# proto.net
KiCad netlist of a schematic drawn in EAGLE
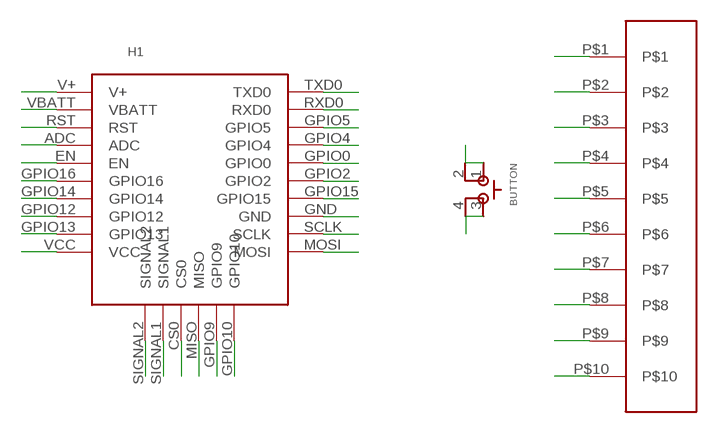
[diagram p0: schematic, sheet 1]

(export (version "E")
  (design (tool "Eeschema 10.0.6"))
  (components
    (comp (ref "BUTTON")
      (value "SKSCLDE010")
      (footprint "eagle-import:SKSCLDE010")
      (libsource (lib "eagle-import") (part "SKSCLDE010"))
    )
    (comp (ref "H1")
      (value "ESP-BOARD")
      (footprint "eagle-import:ESP-BOARD")
      (libsource (lib "eagle-import") (part "ESP-BOARD"))
    )
    (comp (ref "U$1")
      (value "1X10-EDGE")
      (footprint "eagle-import:1X10-EDGE")
      (libsource (lib "eagle-import") (part "1X10-EDGE"))
    )
  )
  (nets
    (net (code "1") (name "Net-(BUTTON-3)") (class "Default")
      (node (ref "BUTTON") (pin "3") (pinfunction "4_3") (pintype "bidirectional"))
      (node (ref "BUTTON") (pin "4") (pinfunction "3_4") (pintype "bidirectional"))
    )
    (net (code "2") (name "Net-(BUTTON-Pad1)") (class "Default")
      (node (ref "BUTTON") (pin "1") (pinfunction "1_1") (pintype "bidirectional"))
      (node (ref "BUTTON") (pin "2") (pinfunction "2_2") (pintype "bidirectional"))
    )
    (net (code "3") (name "unconnected-(H1-PadADC)") (class "Default")
      (node (ref "H1") (pin "ADC") (pinfunction "ADC_ADC") (pintype "bidirectional"))
    )
    (net (code "4") (name "unconnected-(H1-PadCS0)") (class "Default")
      (node (ref "H1") (pin "CS0") (pinfunction "CS0_CS0") (pintype "bidirectional"))
    )
    (net (code "5") (name "unconnected-(H1-PadEN)") (class "Default")
      (node (ref "H1") (pin "EN") (pinfunction "EN_EN") (pintype "bidirectional"))
    )
    (net (code "6") (name "unconnected-(H1-PadGND)") (class "Default")
      (node (ref "H1") (pin "GND") (pinfunction "GND_GND") (pintype "power_in"))
    )
    (net (code "7") (name "unconnected-(H1-PadGPIO0)") (class "Default")
      (node (ref "H1") (pin "GPIO0") (pinfunction "GPIO0_GPIO0") (pintype "bidirectional"))
    )
    (net (code "8") (name "unconnected-(H1-PadGPIO2)") (class "Default")
      (node (ref "H1") (pin "GPIO2") (pinfunction "GPIO2_GPIO2") (pintype "bidirectional"))
    )
    (net (code "9") (name "unconnected-(H1-PadGPIO4)") (class "Default")
      (node (ref "H1") (pin "GPIO4") (pinfunction "GPIO4_GPIO4") (pintype "bidirectional"))
    )
    (net (code "10") (name "unconnected-(H1-PadGPIO5)") (class "Default")
      (node (ref "H1") (pin "GPIO5") (pinfunction "GPIO5_GPIO5") (pintype "bidirectional"))
    )
    (net (code "11") (name "unconnected-(H1-PadGPIO9)") (class "Default")
      (node (ref "H1") (pin "GPIO9") (pinfunction "GPIO9_GPIO9") (pintype "bidirectional"))
    )
    (net (code "12") (name "unconnected-(H1-PadGPIO10)") (class "Default")
      (node (ref "H1") (pin "GPIO10") (pinfunction "GPIO10_GPIO10") (pintype "bidirectional"))
    )
    (net (code "13") (name "unconnected-(H1-PadGPIO12)") (class "Default")
      (node (ref "H1") (pin "GPIO12") (pinfunction "GPIO12_GPIO12") (pintype "bidirectional"))
    )
    (net (code "14") (name "unconnected-(H1-PadGPIO13)") (class "Default")
      (node (ref "H1") (pin "GPIO13") (pinfunction "GPIO13_GPIO13") (pintype "bidirectional"))
    )
    (net (code "15") (name "unconnected-(H1-PadGPIO14)") (class "Default")
      (node (ref "H1") (pin "GPIO14") (pinfunction "GPIO14_GPIO14") (pintype "bidirectional"))
    )
    (net (code "16") (name "unconnected-(H1-PadGPIO15)") (class "Default")
      (node (ref "H1") (pin "GPIO15") (pinfunction "GPIO15_GPIO15") (pintype "bidirectional"))
    )
    (net (code "17") (name "unconnected-(H1-PadGPIO16)") (class "Default")
      (node (ref "H1") (pin "GPIO16") (pinfunction "GPIO16_GPIO16") (pintype "bidirectional"))
    )
    (net (code "18") (name "unconnected-(H1-PadMISO)") (class "Default")
      (node (ref "H1") (pin "MISO") (pinfunction "MISO_MISO") (pintype "bidirectional"))
    )
    (net (code "19") (name "unconnected-(H1-PadMOSI)") (class "Default")
      (node (ref "H1") (pin "MOSI") (pinfunction "MOSI_MOSI") (pintype "bidirectional"))
    )
    (net (code "20") (name "unconnected-(H1-PadRST)") (class "Default")
      (node (ref "H1") (pin "RST") (pinfunction "RST_RST") (pintype "bidirectional"))
    )
    (net (code "21") (name "unconnected-(H1-PadRXD0)") (class "Default")
      (node (ref "H1") (pin "RXD0") (pinfunction "RXD0_RXD0") (pintype "bidirectional"))
    )
    (net (code "22") (name "unconnected-(H1-PadSCLK)") (class "Default")
      (node (ref "H1") (pin "SCLK") (pinfunction "SCLK_SCLK") (pintype "bidirectional"))
    )
    (net (code "23") (name "unconnected-(H1-PadSIGNAL1)") (class "Default")
      (node (ref "H1") (pin "SIGNAL1") (pinfunction "SIGNAL1_SIGNAL1") (pintype "bidirectional"))
    )
    (net (code "24") (name "unconnected-(H1-PadSIGNAL2)") (class "Default")
      (node (ref "H1") (pin "SIGNAL2") (pinfunction "SIGNAL2_SIGNAL2") (pintype "bidirectional"))
    )
    (net (code "25") (name "unconnected-(H1-PadTXD0)") (class "Default")
      (node (ref "H1") (pin "TXD0") (pinfunction "TXD0_TXD0") (pintype "bidirectional"))
    )
    (net (code "26") (name "unconnected-(H1-PadV+)") (class "Default")
      (node (ref "H1") (pin "V+") (pinfunction "V+_V+") (pintype "power_in"))
    )
    (net (code "27") (name "unconnected-(H1-PadVBATT)") (class "Default")
      (node (ref "H1") (pin "VBATT") (pinfunction "VBATT_VBATT") (pintype "power_in"))
    )
    (net (code "28") (name "unconnected-(H1-PadVCC)") (class "Default")
      (node (ref "H1") (pin "VCC") (pinfunction "VCC_VCC") (pintype "power_in"))
    )
    (net (code "29") (name "unconnected-(U$1-PadP$1)") (class "Default")
      (node (ref "U$1") (pin "P$1") (pinfunction "P$1_P$1") (pintype "bidirectional"))
    )
    (net (code "30") (name "unconnected-(U$1-PadP$2)") (class "Default")
      (node (ref "U$1") (pin "P$2") (pinfunction "P$2_P$2") (pintype "bidirectional"))
    )
    (net (code "31") (name "unconnected-(U$1-PadP$3)") (class "Default")
      (node (ref "U$1") (pin "P$3") (pinfunction "P$3_P$3") (pintype "bidirectional"))
    )
    (net (code "32") (name "unconnected-(U$1-PadP$4)") (class "Default")
      (node (ref "U$1") (pin "P$4") (pinfunction "P$4_P$4") (pintype "bidirectional"))
    )
    (net (code "33") (name "unconnected-(U$1-PadP$5)") (class "Default")
      (node (ref "U$1") (pin "P$5") (pinfunction "P$5_P$5") (pintype "bidirectional"))
    )
    (net (code "34") (name "unconnected-(U$1-PadP$6)") (class "Default")
      (node (ref "U$1") (pin "P$6") (pinfunction "P$6_P$6") (pintype "bidirectional"))
    )
    (net (code "35") (name "unconnected-(U$1-PadP$7)") (class "Default")
      (node (ref "U$1") (pin "P$7") (pinfunction "P$7_P$7") (pintype "bidirectional"))
    )
    (net (code "36") (name "unconnected-(U$1-PadP$8)") (class "Default")
      (node (ref "U$1") (pin "P$8") (pinfunction "P$8_P$8") (pintype "bidirectional"))
    )
    (net (code "37") (name "unconnected-(U$1-PadP$9)") (class "Default")
      (node (ref "U$1") (pin "P$9") (pinfunction "P$9_P$9") (pintype "bidirectional"))
    )
    (net (code "38") (name "unconnected-(U$1-PadP$10)") (class "Default")
      (node (ref "U$1") (pin "P$10") (pinfunction "P$10_P$10") (pintype "bidirectional"))
    )
  )
)
